# freedomport.net
KiCad netlist of a schematic drawn in Altium Designer
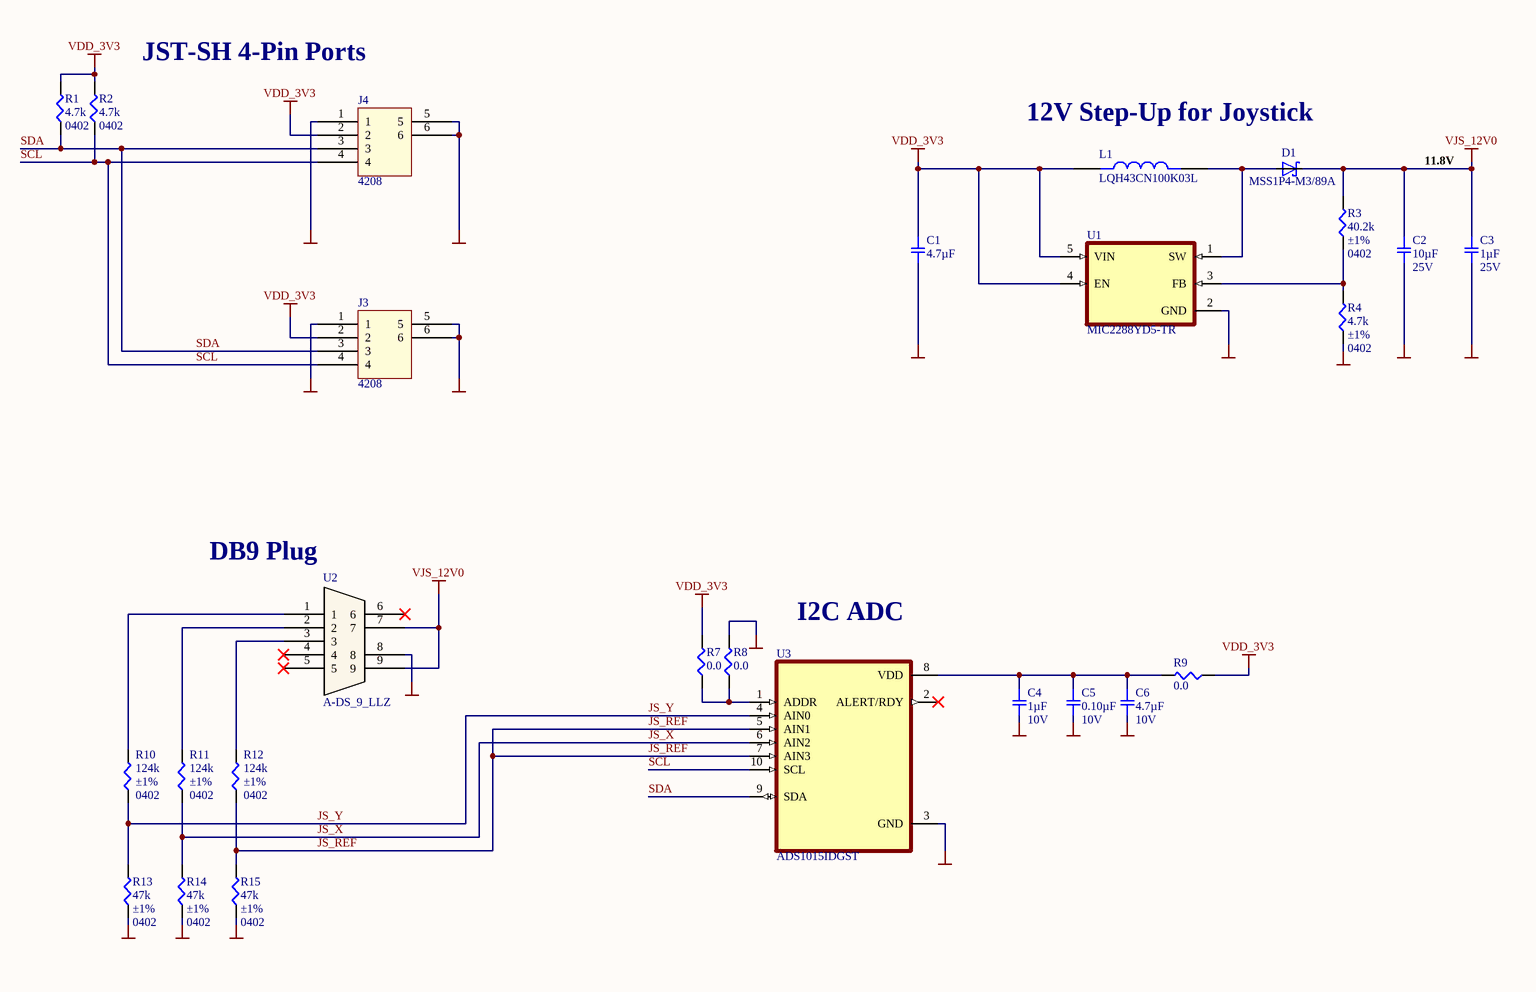
[diagram p0: freedomport.SchDoc]

(export (version "E")
  (design (tool "Eeschema 10.0.6"))
  (components
    (comp (ref "C1")
      (value "4.7µF")
      (footprint "SMD-0603C")
      (description "CAP CER 4.7UF 16V X5R 0603")
      (fields
        (field (name "DIGI-KEY PART NUMBER") "490-10481-1-ND")
        (field (name "PART NUMBER") "GRM188R61C475KAAJD")
      )
      (libsource (lib "cap_murata_0603") (part "GRM188R61C475KAAJD"))
    )
    (comp (ref "C2")
      (value "10µF")
      (footprint "SMD-0603C")
      (description "CAP CER 10UF 25V X5R 0603")
      (fields
        (field (name "DIGI-KEY PART NUMBER") "490-7202-1-ND")
        (field (name "PART NUMBER") "GRM188R61E106MA73D")
        (field (name "VOLTAGE") "25V")
      )
      (libsource (lib "cap_murata_0603") (part "GRM188R61E106MA73D"))
    )
    (comp (ref "C3")
      (value "1µF")
      (footprint "SMD-0402C")
      (description "CAP CER 1UF 25V X5R 0402")
      (fields
        (field (name "DIGI-KEY PART NUMBER") "490-10017-1-ND")
        (field (name "PART NUMBER") "GRM155R61E105KA12D")
        (field (name "VOLTAGE") "25V")
      )
      (libsource (lib "cap_murata_0402") (part "GRM155R61E105KA12D"))
    )
    (comp (ref "C4")
      (value "1µF")
      (footprint "SMD-0402C")
      (description "CAP CER 1UF 10V X5R 0402")
      (fields
        (field (name "DIGI-KEY PART NUMBER") "490-3890-1-ND")
        (field (name "PART NUMBER") "GRM155R61A105KE15D")
        (field (name "VOLTAGE") "10V")
      )
      (libsource (lib "cap_murata_0402") (part "GRM155R61A105KE15D"))
    )
    (comp (ref "C5")
      (value "0.10µF")
      (footprint "SMD-0402C")
      (description "CAP CER 0.1UF 10V X5R 0402")
      (fields
        (field (name "DIGI-KEY PART NUMBER") "490-10008-1-ND")
        (field (name "PART NUMBER") "GRM152R61A104KE19D")
        (field (name "VOLTAGE") "10V")
      )
      (libsource (lib "cap_murata_0402") (part "GRM152R61A104KE19D"))
    )
    (comp (ref "C6")
      (value "4.7µF")
      (footprint "SMD-0402C")
      (description "CAP CER 4.7UF 10V X5R 0402")
      (fields
        (field (name "DIGI-KEY PART NUMBER") "490-13252-1-ND")
        (field (name "PART NUMBER") "ZRB15XR61A475KE01D")
        (field (name "VOLTAGE") "10V")
      )
      (libsource (lib "cap_murata_0402") (part "ZRB15XR61A475KE01D"))
    )
    (comp (ref "D1")
      (value "MSS1P4-M3/89A")
      (footprint "DIODE_MSS1P4-M3/89A")
      (description "Diode Schottky 40V 1A Surface Mount MicroSMP (DO-219AD)")
      (fields (field (name "DIGI-KEY_PART_NUMBER") "MSS1P4-M3/89AGICT-ND") (field (name "MF") "Vishay"))
      (libsource (lib "MSS1P4-M3_89A") (part "MSS1P4-M3/89A"))
    )
    (comp (ref "J3") (value "4208") (footprint "JST-SH:4208") (libsource (lib "JST-SH") (part "4208")))
    (comp (ref "J4") (value "4208") (footprint "JST-SH:4208") (libsource (lib "JST-SH") (part "4208")))
    (comp (ref "L1")
      (value "LQH43CN100K03L")
      (footprint "IND_LQH43CN100K03L")
      (description "Inductor with Inductance: 10uH Tol. +/-10%, Package: 1812 _4532_")
      (fields (field (name "MF") "Murata"))
      (libsource (lib "LQH43CN100K03L") (part "LQH43CN100K03L"))
    )
    (comp (ref "R1")
      (value "4.7k")
      (footprint "SMD-0402-RES")
      (description "RES SMD 4.7K OHM 5% 1/10W 0402")
      (fields
        (field (name "PART NUMBER") "ERJ-2GEJ472X")
        (field (name "DIGI-KEY PART NUMBER") "P4.7KJCT-ND")
        (field (name "SUPPLIER DEVICE PACKAGE") "0402")
      )
      (libsource (lib "res_0402_panasonic_ERJ") (part "ERJ-2GEJ472X"))
    )
    (comp (ref "R2")
      (value "4.7k")
      (footprint "SMD-0402-RES")
      (description "RES SMD 4.7K OHM 5% 1/10W 0402")
      (fields
        (field (name "PART NUMBER") "ERJ-2GEJ472X")
        (field (name "DIGI-KEY PART NUMBER") "P4.7KJCT-ND")
        (field (name "SUPPLIER DEVICE PACKAGE") "0402")
      )
      (libsource (lib "res_0402_panasonic_ERJ") (part "ERJ-2GEJ472X"))
    )
    (comp (ref "R3")
      (value "40.2k")
      (footprint "SMD-0402-RES")
      (description "RES SMD 40.2K OHM 1% 1/10W 0402")
      (fields
        (field (name "PART NUMBER") "ERJ-2RKF4022X")
        (field (name "DIGI-KEY PART NUMBER") "P40.2KLCT-ND")
        (field (name "TOLERANCE") "±1%")
        (field (name "SUPPLIER DEVICE PACKAGE") "0402")
      )
      (libsource (lib "res_0402_panasonic_ERJ") (part "ERJ-2RKF4022X"))
    )
    (comp (ref "R4")
      (value "4.7k")
      (footprint "SMD-0402-RES")
      (description "RES SMD 4.7K OHM 1% 1/10W 0402")
      (fields
        (field (name "PART NUMBER") "ERJ-2RKF4701X")
        (field (name "DIGI-KEY PART NUMBER") "P4.70KLCT-ND")
        (field (name "TOLERANCE") "±1%")
        (field (name "SUPPLIER DEVICE PACKAGE") "0402")
      )
      (libsource (lib "res_0402_panasonic_ERJ") (part "ERJ-2RKF4701X"))
    )
    (comp (ref "R7")
      (value "0.0")
      (footprint "SMD-0402-RES")
      (description "RES SMD 0.0OHM JUMPER 1/10W 0402")
      (fields (field (name "PART NUMBER") "ERJ-2GE0R00X") (field (name "DIGI-KEY PART NUMBER") "P0.0JCT-ND"))
      (libsource (lib "res_0402_panasonic_ERJ") (part "ERJ-2GE0R00X"))
    )
    (comp (ref "R8")
      (value "0.0")
      (footprint "SMD-0402-RES")
      (description "RES SMD 0.0OHM JUMPER 1/10W 0402")
      (fields (field (name "PART NUMBER") "ERJ-2GE0R00X") (field (name "DIGI-KEY PART NUMBER") "P0.0JCT-ND"))
      (libsource (lib "res_0402_panasonic_ERJ") (part "ERJ-2GE0R00X"))
    )
    (comp (ref "R9")
      (value "0.0")
      (footprint "SMD-0402-RES")
      (description "RES SMD 0.0OHM JUMPER 1/10W 0402")
      (fields (field (name "PART NUMBER") "ERJ-2GE0R00X") (field (name "DIGI-KEY PART NUMBER") "P0.0JCT-ND"))
      (libsource (lib "res_0402_panasonic_ERJ") (part "ERJ-2GE0R00X"))
    )
    (comp (ref "R10")
      (value "124k")
      (footprint "SMD-0402-RES")
      (description "RES SMD 124K OHM 1% 1/10W 0402")
      (fields
        (field (name "PART NUMBER") "ERJ-2RKF1243X")
        (field (name "DIGI-KEY PART NUMBER") "P124KLCT-ND")
        (field (name "TOLERANCE") "±1%")
        (field (name "SUPPLIER DEVICE PACKAGE") "0402")
      )
      (libsource (lib "res_0402_panasonic_ERJ") (part "ERJ-2RKF1243X"))
    )
    (comp (ref "R11")
      (value "124k")
      (footprint "SMD-0402-RES")
      (description "RES SMD 124K OHM 1% 1/10W 0402")
      (fields
        (field (name "PART NUMBER") "ERJ-2RKF1243X")
        (field (name "DIGI-KEY PART NUMBER") "P124KLCT-ND")
        (field (name "TOLERANCE") "±1%")
        (field (name "SUPPLIER DEVICE PACKAGE") "0402")
      )
      (libsource (lib "res_0402_panasonic_ERJ") (part "ERJ-2RKF1243X"))
    )
    (comp (ref "R12")
      (value "124k")
      (footprint "SMD-0402-RES")
      (description "RES SMD 124K OHM 1% 1/10W 0402")
      (fields
        (field (name "PART NUMBER") "ERJ-2RKF1243X")
        (field (name "DIGI-KEY PART NUMBER") "P124KLCT-ND")
        (field (name "TOLERANCE") "±1%")
        (field (name "SUPPLIER DEVICE PACKAGE") "0402")
      )
      (libsource (lib "res_0402_panasonic_ERJ") (part "ERJ-2RKF1243X"))
    )
    (comp (ref "R13")
      (value "47k")
      (footprint "SMD-0402-RES")
      (description "RES SMD 47K OHM 1% 1/10W 0402")
      (fields
        (field (name "PART NUMBER") "ERJ-2RKF4702X")
        (field (name "DIGI-KEY PART NUMBER") "P47.0KLCT-ND")
        (field (name "TOLERANCE") "±1%")
        (field (name "SUPPLIER DEVICE PACKAGE") "0402")
      )
      (libsource (lib "res_0402_panasonic_ERJ") (part "ERJ-2RKF4702X"))
    )
    (comp (ref "R14")
      (value "47k")
      (footprint "SMD-0402-RES")
      (description "RES SMD 47K OHM 1% 1/10W 0402")
      (fields
        (field (name "PART NUMBER") "ERJ-2RKF4702X")
        (field (name "DIGI-KEY PART NUMBER") "P47.0KLCT-ND")
        (field (name "TOLERANCE") "±1%")
        (field (name "SUPPLIER DEVICE PACKAGE") "0402")
      )
      (libsource (lib "res_0402_panasonic_ERJ") (part "ERJ-2RKF4702X"))
    )
    (comp (ref "R15")
      (value "47k")
      (footprint "SMD-0402-RES")
      (description "RES SMD 47K OHM 1% 1/10W 0402")
      (fields
        (field (name "PART NUMBER") "ERJ-2RKF4702X")
        (field (name "DIGI-KEY PART NUMBER") "P47.0KLCT-ND")
        (field (name "TOLERANCE") "±1%")
        (field (name "SUPPLIER DEVICE PACKAGE") "0402")
      )
      (libsource (lib "res_0402_panasonic_ERJ") (part "ERJ-2RKF4702X"))
    )
    (comp (ref "U1")
      (value "MIC2288YD5-TR")
      (footprint "SOT95P280X100-5N")
      (fields (field (name "MF") "Microchip"))
      (libsource (lib "MIC2288YD5-TR") (part "MIC2288YD5-TR"))
    )
    (comp (ref "U2")
      (value "A-DS_9_LLZ")
      (footprint "A-DS_9_LLZ:A-DS_9_LLZ")
      (libsource (lib "A-DS_9_LLZ") (part "A-DS_9_LLZ"))
    )
    (comp (ref "U3")
      (value "ADS1015IDGST")
      (footprint "SOP50P490X110-10N")
      (fields
        (field (name "MF") "Texas Instruments")
        (field (name "BUYPART") "https://www.snapeda.com/parts/ADS1015IDGST/Texas%20Instruments/view-part/425936/?ref=eda")
      )
      (libsource (lib "ADS1015IDGST") (part "ADS1015IDGST"))
    )
  )
  (nets
    (net (code "1") (name "/JS_REF") (class "Default")
      (node (ref "R12") (pin "1") (pinfunction "1_1") (pintype "passive"))
      (node (ref "R15") (pin "2") (pinfunction "2_2") (pintype "passive"))
      (node (ref "U3") (pin "5") (pinfunction "AIN1_5") (pintype "input"))
      (node (ref "U3") (pin "7") (pinfunction "AIN3_7") (pintype "input"))
    )
    (net (code "2") (name "/JS_X") (class "Default")
      (node (ref "R11") (pin "1") (pinfunction "1_1") (pintype "passive"))
      (node (ref "R14") (pin "2") (pinfunction "2_2") (pintype "passive"))
      (node (ref "U3") (pin "6") (pinfunction "AIN2_6") (pintype "input"))
    )
    (net (code "3") (name "/JS_Y") (class "Default")
      (node (ref "R10") (pin "1") (pinfunction "1_1") (pintype "passive"))
      (node (ref "R13") (pin "2") (pinfunction "2_2") (pintype "passive"))
      (node (ref "U3") (pin "4") (pinfunction "AIN0_4") (pintype "input"))
    )
    (net (code "4") (name "/SCL") (class "Default")
      (node (ref "J3") (pin "4") (pinfunction "4_4") (pintype "passive"))
      (node (ref "J4") (pin "4") (pinfunction "4_4") (pintype "passive"))
      (node (ref "R2") (pin "1") (pinfunction "1_1") (pintype "passive"))
      (node (ref "U3") (pin "10") (pinfunction "SCL_10") (pintype "input"))
    )
    (net (code "5") (name "/SDA") (class "Default")
      (node (ref "J3") (pin "3") (pinfunction "3_3") (pintype "passive"))
      (node (ref "J4") (pin "3") (pinfunction "3_3") (pintype "passive"))
      (node (ref "R1") (pin "1") (pinfunction "1_1") (pintype "passive"))
      (node (ref "U3") (pin "9") (pinfunction "SDA_9") (pintype "bidirectional"))
    )
    (net (code "6") (name "GND") (class "Default")
      (node (ref "C1") (pin "2") (pinfunction "2_2") (pintype "passive"))
      (node (ref "C2") (pin "2") (pinfunction "2_2") (pintype "passive"))
      (node (ref "C3") (pin "2") (pinfunction "2_2") (pintype "passive"))
      (node (ref "C4") (pin "2") (pinfunction "2_2") (pintype "passive"))
      (node (ref "C5") (pin "2") (pinfunction "2_2") (pintype "passive"))
      (node (ref "C6") (pin "2") (pinfunction "2_2") (pintype "passive"))
      (node (ref "J3") (pin "1") (pinfunction "1_1") (pintype "passive"))
      (node (ref "J3") (pin "5") (pinfunction "5_5") (pintype "passive"))
      (node (ref "J3") (pin "6") (pinfunction "6_6") (pintype "passive"))
      (node (ref "J4") (pin "1") (pinfunction "1_1") (pintype "passive"))
      (node (ref "J4") (pin "5") (pinfunction "5_5") (pintype "passive"))
      (node (ref "J4") (pin "6") (pinfunction "6_6") (pintype "passive"))
      (node (ref "R13") (pin "1") (pinfunction "1_1") (pintype "passive"))
      (node (ref "R14") (pin "1") (pinfunction "1_1") (pintype "passive"))
      (node (ref "R15") (pin "1") (pinfunction "1_1") (pintype "passive"))
      (node (ref "R4") (pin "1") (pinfunction "1_1") (pintype "passive"))
      (node (ref "R8") (pin "2") (pinfunction "2_2") (pintype "passive"))
      (node (ref "U1") (pin "2") (pinfunction "GND_2") (pintype "power_in"))
      (node (ref "U2") (pin "8") (pinfunction "8_8") (pintype "passive"))
      (node (ref "U3") (pin "3") (pinfunction "GND_3") (pintype "power_in"))
    )
    (net (code "7") (name "Net-(D1-A)") (class "Default")
      (node (ref "D1") (pin "2") (pinfunction "A_2") (pintype "passive"))
      (node (ref "L1") (pin "2") (pinfunction "2_2") (pintype "passive"))
      (node (ref "U1") (pin "1") (pinfunction "SW_1") (pintype "input"))
    )
    (net (code "8") (name "Net-(R10-Pad2)") (class "Default")
      (node (ref "R10") (pin "2") (pinfunction "2_2") (pintype "passive"))
      (node (ref "U2") (pin "1") (pinfunction "1_1") (pintype "passive"))
    )
    (net (code "9") (name "Net-(R11-Pad2)") (class "Default")
      (node (ref "R11") (pin "2") (pinfunction "2_2") (pintype "passive"))
      (node (ref "U2") (pin "2") (pinfunction "2_2") (pintype "passive"))
    )
    (net (code "10") (name "Net-(R12-Pad2)") (class "Default")
      (node (ref "R12") (pin "2") (pinfunction "2_2") (pintype "passive"))
      (node (ref "U2") (pin "3") (pinfunction "3_3") (pintype "passive"))
    )
    (net (code "11") (name "Net-(U1-FB)") (class "Default")
      (node (ref "R3") (pin "1") (pinfunction "1_1") (pintype "passive"))
      (node (ref "R4") (pin "2") (pinfunction "2_2") (pintype "passive"))
      (node (ref "U1") (pin "3") (pinfunction "FB_3") (pintype "input"))
    )
    (net (code "12") (name "Net-(U3-ADDR)") (class "Default")
      (node (ref "R7") (pin "1") (pinfunction "1_1") (pintype "passive"))
      (node (ref "R8") (pin "1") (pinfunction "1_1") (pintype "passive"))
      (node (ref "U3") (pin "1") (pinfunction "ADDR_1") (pintype "input"))
    )
    (net (code "13") (name "Net-(U3-VDD)") (class "Default")
      (node (ref "C4") (pin "1") (pinfunction "1_1") (pintype "passive"))
      (node (ref "C5") (pin "1") (pinfunction "1_1") (pintype "passive"))
      (node (ref "C6") (pin "1") (pinfunction "1_1") (pintype "passive"))
      (node (ref "R9") (pin "2") (pinfunction "2_2") (pintype "passive"))
      (node (ref "U3") (pin "8") (pinfunction "VDD_8") (pintype "power_in"))
    )
    (net (code "14") (name "VDD_3V3") (class "Default")
      (node (ref "C1") (pin "1") (pinfunction "1_1") (pintype "passive"))
      (node (ref "J3") (pin "2") (pinfunction "2_2") (pintype "passive"))
      (node (ref "J4") (pin "2") (pinfunction "2_2") (pintype "passive"))
      (node (ref "L1") (pin "1") (pinfunction "1_1") (pintype "passive"))
      (node (ref "R1") (pin "2") (pinfunction "2_2") (pintype "passive"))
      (node (ref "R2") (pin "2") (pinfunction "2_2") (pintype "passive"))
      (node (ref "R7") (pin "2") (pinfunction "2_2") (pintype "passive"))
      (node (ref "R9") (pin "1") (pinfunction "1_1") (pintype "passive"))
      (node (ref "U1") (pin "4") (pinfunction "EN_4") (pintype "input"))
      (node (ref "U1") (pin "5") (pinfunction "VIN_5") (pintype "input"))
    )
    (net (code "15") (name "VJS_12V0") (class "Default")
      (node (ref "C2") (pin "1") (pinfunction "1_1") (pintype "passive"))
      (node (ref "C3") (pin "1") (pinfunction "1_1") (pintype "passive"))
      (node (ref "D1") (pin "1") (pinfunction "C_1") (pintype "passive"))
      (node (ref "R3") (pin "2") (pinfunction "2_2") (pintype "passive"))
      (node (ref "U2") (pin "7") (pinfunction "7_7") (pintype "passive"))
      (node (ref "U2") (pin "9") (pinfunction "9_9") (pintype "passive"))
    )
    (net (code "16") (name "unconnected-(U2-Pad4)") (class "Default")
      (node (ref "U2") (pin "4") (pinfunction "4_4") (pintype "passive+no_connect"))
    )
    (net (code "17") (name "unconnected-(U2-Pad5)") (class "Default")
      (node (ref "U2") (pin "5") (pinfunction "5_5") (pintype "passive+no_connect"))
    )
    (net (code "18") (name "unconnected-(U2-Pad6)") (class "Default")
      (node (ref "U2") (pin "6") (pinfunction "6_6") (pintype "passive+no_connect"))
    )
    (net (code "19") (name "unconnected-(U3-ALERT{slash}RDY-Pad2)") (class "Default")
      (node (ref "U3") (pin "2") (pinfunction "ALERT/RDY_2") (pintype "output+no_connect"))
    )
  )
)
